# Top.net
KiCad netlist of a schematic drawn in Altium Designer
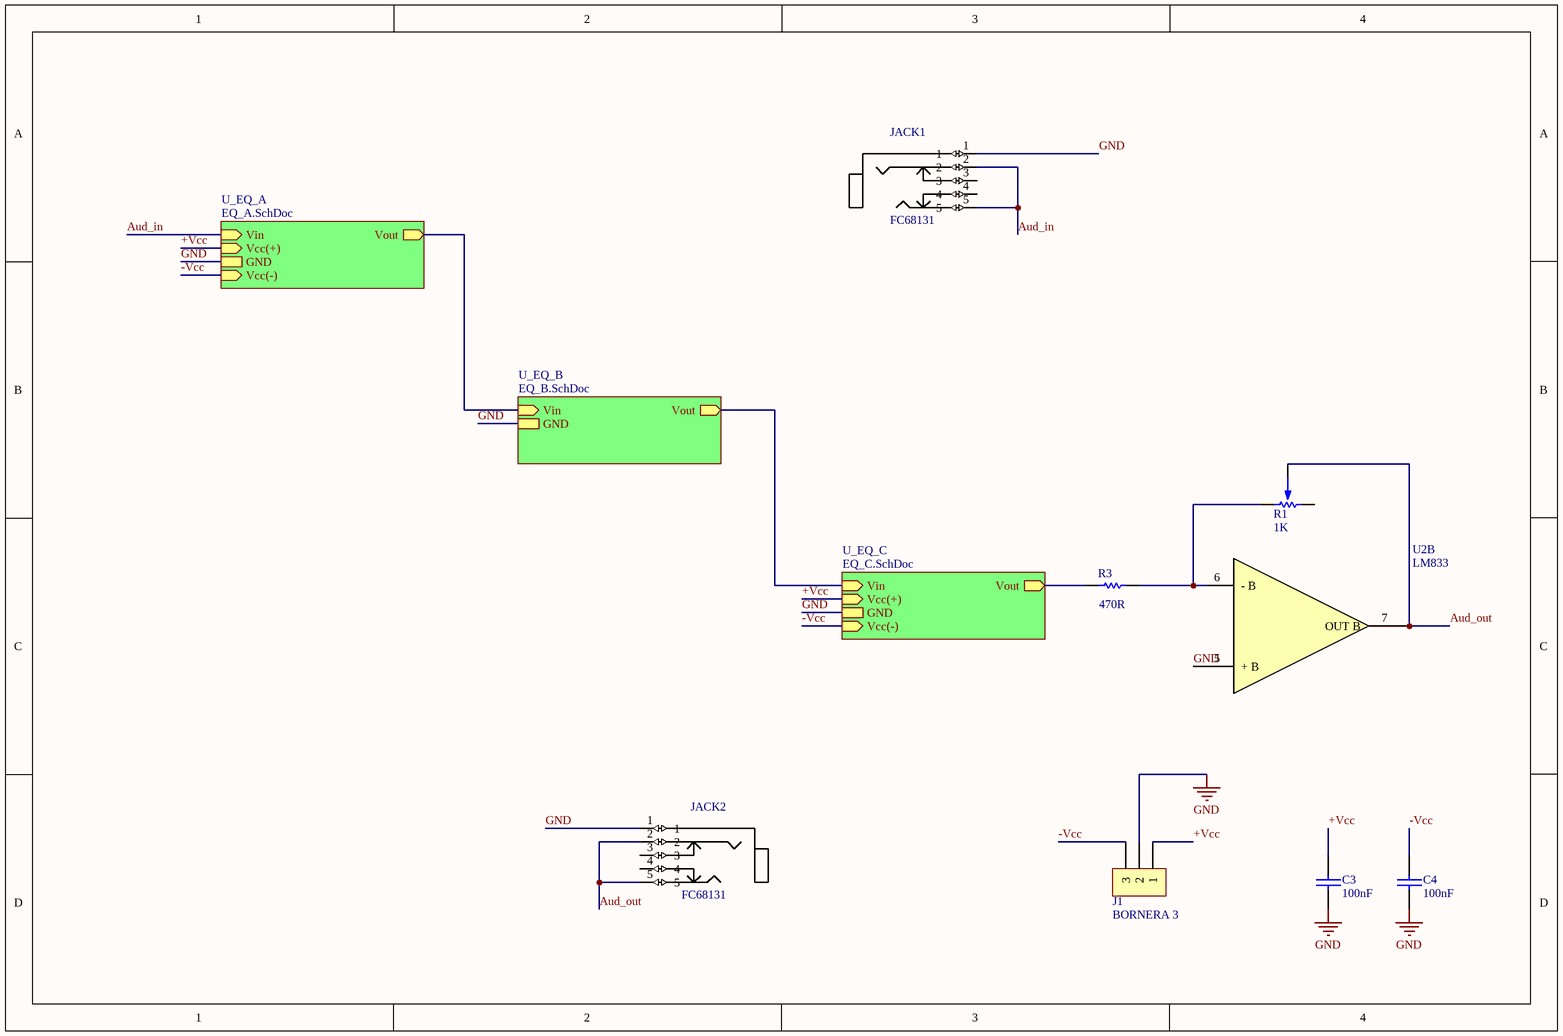
[diagram p0: Top.SchDoc]

(export (version "E")
  (design (tool "Eeschema 10.0.6"))
  (components
    (comp (ref "C3") (value "100nF") (footprint "CAP200") (libsource (lib "LIBEBAL") (part "CAP")))
    (comp (ref "C4") (value "100nF") (footprint "CAP200") (libsource (lib "LIBEBAL") (part "CAP")))
    (comp (ref "J1")
      (value "BORNERA 3")
      (footprint "BORNERA3")
      (libsource (lib "LIBEBAL") (part "BORNERA 3"))
    )
    (comp (ref "JACK1")
      (value "FC68131")
      (footprint "*FC68131-5P")
      (description "Stereo Jack, 3.5mm, 3pos, Pcb")
      (fields (field (name "MF") "Cliff"))
      (libsource (lib "FC68131") (part "FC68131"))
    )
    (comp (ref "JACK2")
      (value "FC68131")
      (footprint "*FC68131-5P")
      (description "Stereo Jack, 3.5mm, 3pos, Pcb")
      (fields (field (name "MF") "Cliff"))
      (libsource (lib "FC68131") (part "FC68131"))
    )
    (comp (ref "R1")
      (value "1K")
      (footprint "POTENCIOMETRO")
      (libsource (lib "LIBEBAL") (part "POTENCIOMETRO"))
    )
    (comp (ref "R3") (value "470R") (footprint "0805") (libsource (lib "LIBEBAL") (part "RES")))
    (comp (ref "U2")
      (value "LM833")
      (footprint "DIP8")
      (description "Dual Audio Operational Amplifier")
      (libsource (lib "LIBEBAL") (part "LM833"))
    )
  )
  (nets
    (net (code "1") (name "/+Vcc") (class "Default")
      (node (ref "C3") (pin "1") (pinfunction "1_1") (pintype "passive"))
      (node (ref "J1") (pin "1") (pinfunction "1_1") (pintype "passive"))
    )
    (net (code "2") (name "/-Vcc") (class "Default")
      (node (ref "C4") (pin "2") (pinfunction "2_2") (pintype "passive"))
      (node (ref "J1") (pin "3") (pinfunction "3_3") (pintype "passive"))
    )
    (net (code "3") (name "/Aud_in") (class "Default")
      (node (ref "JACK1") (pin "2") (pinfunction "2_2") (pintype "bidirectional"))
      (node (ref "JACK1") (pin "5") (pinfunction "5_5") (pintype "bidirectional"))
    )
    (net (code "4") (name "/Aud_out") (class "Default")
      (node (ref "JACK2") (pin "2") (pinfunction "2_2") (pintype "bidirectional"))
      (node (ref "JACK2") (pin "5") (pinfunction "5_5") (pintype "bidirectional"))
      (node (ref "R1") (pin "2") (pinfunction "2_2") (pintype "passive"))
      (node (ref "U2") (pin "7") (pinfunction "OUT_B_7") (pintype "passive"))
    )
    (net (code "6") (name "/Vout_1") (class "Default")
      (node (ref "R3") (pin "1") (pinfunction "1_1") (pintype "passive"))
    )
    (net (code "8") (name "GND") (class "Default")
      (node (ref "C3") (pin "2") (pinfunction "2_2") (pintype "passive"))
      (node (ref "C4") (pin "1") (pinfunction "1_1") (pintype "passive"))
      (node (ref "J1") (pin "2") (pinfunction "2_2") (pintype "passive"))
      (node (ref "JACK1") (pin "1") (pinfunction "1_1") (pintype "bidirectional"))
      (node (ref "JACK2") (pin "1") (pinfunction "1_1") (pintype "bidirectional"))
      (node (ref "U2") (pin "5") (pinfunction "+_B_5") (pintype "passive"))
    )
    (net (code "9") (name "Net-(U2B--_B)") (class "Default")
      (node (ref "R1") (pin "1") (pinfunction "1_1") (pintype "passive"))
      (node (ref "R3") (pin "2") (pinfunction "2_2") (pintype "passive"))
      (node (ref "U2") (pin "6") (pinfunction "-_B_6") (pintype "passive"))
    )
    (net (code "10") (name "unconnected-(JACK1-Pad3)") (class "Default")
      (node (ref "JACK1") (pin "3") (pinfunction "3_3") (pintype "bidirectional"))
    )
    (net (code "11") (name "unconnected-(JACK1-Pad4)") (class "Default")
      (node (ref "JACK1") (pin "4") (pinfunction "4_4") (pintype "bidirectional"))
    )
    (net (code "12") (name "unconnected-(JACK2-Pad3)") (class "Default")
      (node (ref "JACK2") (pin "3") (pinfunction "3_3") (pintype "bidirectional"))
    )
    (net (code "13") (name "unconnected-(JACK2-Pad4)") (class "Default")
      (node (ref "JACK2") (pin "4") (pinfunction "4_4") (pintype "bidirectional"))
    )
    (net (code "14") (name "unconnected-(R1-Pad3)") (class "Default")
      (node (ref "R1") (pin "3") (pinfunction "3_3") (pintype "passive"))
    )
  )
)
